# tree1.net
KiCad netlist of a schematic drawn in EAGLE
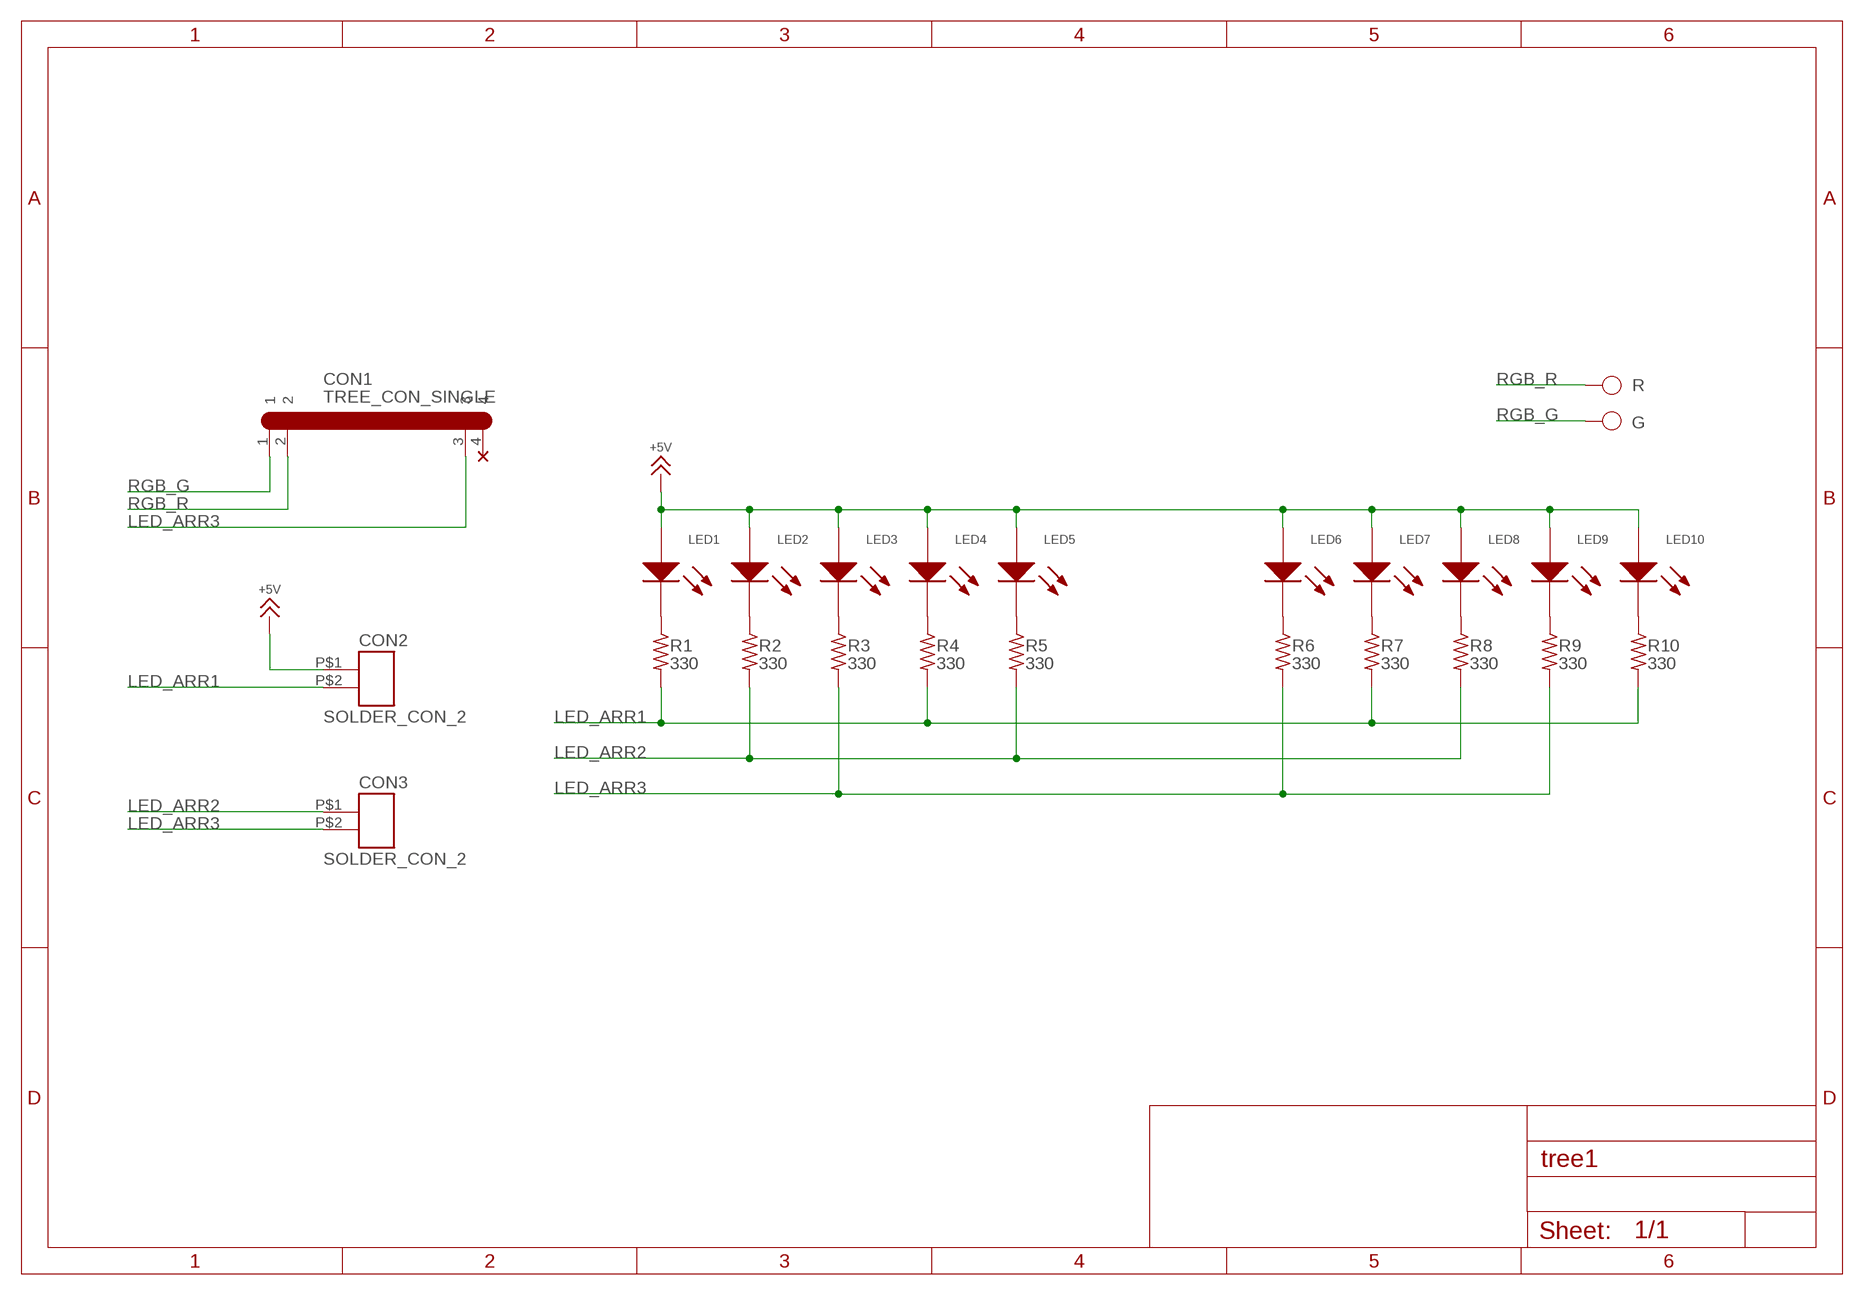
[diagram p0: schematic, sheet 1]

(export (version "E")
  (design (tool "Eeschema 10.0.6"))
  (components
    (comp (ref "CON1")
      (value "TREE_CON_SINGLE")
      (footprint "eagle-import:TREE_CON_SINGLE")
      (libsource (lib "eagle-import") (part "TREE_CON_SINGLE"))
    )
    (comp (ref "CON2")
      (value "SOLDER_CON_2")
      (footprint "eagle-import:SOLDER_CON_2")
      (libsource (lib "eagle-import") (part "SOLDER_CON_2"))
    )
    (comp (ref "CON3")
      (value "SOLDER_CON_2")
      (footprint "eagle-import:SOLDER_CON_2")
      (libsource (lib "eagle-import") (part "SOLDER_CON_2"))
    )
    (comp (ref "G") (value "TP") (footprint "eagle-import:TP") (libsource (lib "eagle-import") (part "TP")))
    (comp (ref "LED1")
      (value "LED_BEN")
      (footprint "eagle-import:LED_5MM_BEN")
      (libsource (lib "eagle-import") (part "LED_BEN"))
    )
    (comp (ref "LED2")
      (value "LED_BEN")
      (footprint "eagle-import:LED_5MM_BEN")
      (libsource (lib "eagle-import") (part "LED_BEN"))
    )
    (comp (ref "LED3")
      (value "LED_BEN")
      (footprint "eagle-import:LED_5MM_BEN")
      (libsource (lib "eagle-import") (part "LED_BEN"))
    )
    (comp (ref "LED4")
      (value "LED_BEN")
      (footprint "eagle-import:LED_5MM_BEN")
      (libsource (lib "eagle-import") (part "LED_BEN"))
    )
    (comp (ref "LED5")
      (value "LED_BEN")
      (footprint "eagle-import:LED_5MM_BEN")
      (libsource (lib "eagle-import") (part "LED_BEN"))
    )
    (comp (ref "LED6")
      (value "LED_BEN")
      (footprint "eagle-import:LED_5MM_BEN")
      (libsource (lib "eagle-import") (part "LED_BEN"))
    )
    (comp (ref "LED7")
      (value "LED_BEN")
      (footprint "eagle-import:LED_5MM_BEN")
      (libsource (lib "eagle-import") (part "LED_BEN"))
    )
    (comp (ref "LED8")
      (value "LED_BEN")
      (footprint "eagle-import:LED_5MM_BEN")
      (libsource (lib "eagle-import") (part "LED_BEN"))
    )
    (comp (ref "LED9")
      (value "LED_BEN")
      (footprint "eagle-import:LED_5MM_BEN")
      (libsource (lib "eagle-import") (part "LED_BEN"))
    )
    (comp (ref "LED10")
      (value "LED_BEN")
      (footprint "eagle-import:LED_5MM_BEN")
      (libsource (lib "eagle-import") (part "LED_BEN"))
    )
    (comp (ref "R") (value "TP") (footprint "eagle-import:TP") (libsource (lib "eagle-import") (part "TP")))
    (comp (ref "R1")
      (value "330")
      (footprint "eagle-import:SMD2012")
      (libsource (lib "eagle-import") (part "RES_2012"))
    )
    (comp (ref "R2")
      (value "330")
      (footprint "eagle-import:SMD2012")
      (libsource (lib "eagle-import") (part "RES_2012"))
    )
    (comp (ref "R3")
      (value "330")
      (footprint "eagle-import:SMD2012")
      (libsource (lib "eagle-import") (part "RES_2012"))
    )
    (comp (ref "R4")
      (value "330")
      (footprint "eagle-import:SMD2012")
      (libsource (lib "eagle-import") (part "RES_2012"))
    )
    (comp (ref "R5")
      (value "330")
      (footprint "eagle-import:SMD2012")
      (libsource (lib "eagle-import") (part "RES_2012"))
    )
    (comp (ref "R6")
      (value "330")
      (footprint "eagle-import:SMD2012")
      (libsource (lib "eagle-import") (part "RES_2012"))
    )
    (comp (ref "R7")
      (value "330")
      (footprint "eagle-import:SMD2012")
      (libsource (lib "eagle-import") (part "RES_2012"))
    )
    (comp (ref "R8")
      (value "330")
      (footprint "eagle-import:SMD2012")
      (libsource (lib "eagle-import") (part "RES_2012"))
    )
    (comp (ref "R9")
      (value "330")
      (footprint "eagle-import:SMD2012")
      (libsource (lib "eagle-import") (part "RES_2012"))
    )
    (comp (ref "R10")
      (value "330")
      (footprint "eagle-import:SMD2012")
      (libsource (lib "eagle-import") (part "RES_2012"))
    )
  )
  (nets
    (net (code "1") (name "+5V") (class "Default")
      (node (ref "CON2") (pin "P$1") (pinfunction "P$1_P$1") (pintype "passive"))
      (node (ref "LED1") (pin "1") (pinfunction "P$1_1") (pintype "passive"))
      (node (ref "LED10") (pin "1") (pinfunction "P$1_1") (pintype "passive"))
      (node (ref "LED2") (pin "1") (pinfunction "P$1_1") (pintype "passive"))
      (node (ref "LED3") (pin "1") (pinfunction "P$1_1") (pintype "passive"))
      (node (ref "LED4") (pin "1") (pinfunction "P$1_1") (pintype "passive"))
      (node (ref "LED5") (pin "1") (pinfunction "P$1_1") (pintype "passive"))
      (node (ref "LED6") (pin "1") (pinfunction "P$1_1") (pintype "passive"))
      (node (ref "LED7") (pin "1") (pinfunction "P$1_1") (pintype "passive"))
      (node (ref "LED8") (pin "1") (pinfunction "P$1_1") (pintype "passive"))
      (node (ref "LED9") (pin "1") (pinfunction "P$1_1") (pintype "passive"))
    )
    (net (code "2") (name "/LED_ARR1") (class "Default")
      (node (ref "CON2") (pin "P$2") (pinfunction "P$2_P$2") (pintype "passive"))
      (node (ref "R1") (pin "2") (pinfunction "2_2") (pintype "passive"))
      (node (ref "R10") (pin "2") (pinfunction "2_2") (pintype "passive"))
      (node (ref "R4") (pin "2") (pinfunction "2_2") (pintype "passive"))
      (node (ref "R7") (pin "2") (pinfunction "2_2") (pintype "passive"))
    )
    (net (code "3") (name "/LED_ARR2") (class "Default")
      (node (ref "CON3") (pin "P$1") (pinfunction "P$1_P$1") (pintype "passive"))
      (node (ref "R2") (pin "2") (pinfunction "2_2") (pintype "passive"))
      (node (ref "R5") (pin "2") (pinfunction "2_2") (pintype "passive"))
      (node (ref "R8") (pin "2") (pinfunction "2_2") (pintype "passive"))
    )
    (net (code "4") (name "/LED_ARR3") (class "Default")
      (node (ref "CON1") (pin "3") (pinfunction "3_3") (pintype "passive"))
      (node (ref "CON3") (pin "P$2") (pinfunction "P$2_P$2") (pintype "passive"))
      (node (ref "R3") (pin "2") (pinfunction "2_2") (pintype "passive"))
      (node (ref "R6") (pin "2") (pinfunction "2_2") (pintype "passive"))
      (node (ref "R9") (pin "2") (pinfunction "2_2") (pintype "passive"))
    )
    (net (code "5") (name "/RGB_G") (class "Default")
      (node (ref "CON1") (pin "1") (pinfunction "1_1") (pintype "passive"))
      (node (ref "G") (pin "1") (pinfunction "P$1_1") (pintype "passive"))
    )
    (net (code "6") (name "/RGB_R") (class "Default")
      (node (ref "CON1") (pin "2") (pinfunction "2_2") (pintype "passive"))
      (node (ref "R") (pin "1") (pinfunction "P$1_1") (pintype "passive"))
    )
    (net (code "7") (name "Net-(LED1-P$2)") (class "Default")
      (node (ref "LED1") (pin "2") (pinfunction "P$2_2") (pintype "passive"))
      (node (ref "R1") (pin "1") (pinfunction "1_1") (pintype "passive"))
    )
    (net (code "8") (name "Net-(LED2-P$2)") (class "Default")
      (node (ref "LED2") (pin "2") (pinfunction "P$2_2") (pintype "passive"))
      (node (ref "R2") (pin "1") (pinfunction "1_1") (pintype "passive"))
    )
    (net (code "9") (name "Net-(LED3-P$2)") (class "Default")
      (node (ref "LED3") (pin "2") (pinfunction "P$2_2") (pintype "passive"))
      (node (ref "R3") (pin "1") (pinfunction "1_1") (pintype "passive"))
    )
    (net (code "10") (name "Net-(LED4-P$2)") (class "Default")
      (node (ref "LED4") (pin "2") (pinfunction "P$2_2") (pintype "passive"))
      (node (ref "R4") (pin "1") (pinfunction "1_1") (pintype "passive"))
    )
    (net (code "11") (name "Net-(LED5-P$2)") (class "Default")
      (node (ref "LED5") (pin "2") (pinfunction "P$2_2") (pintype "passive"))
      (node (ref "R5") (pin "1") (pinfunction "1_1") (pintype "passive"))
    )
    (net (code "12") (name "Net-(LED6-P$2)") (class "Default")
      (node (ref "LED6") (pin "2") (pinfunction "P$2_2") (pintype "passive"))
      (node (ref "R6") (pin "1") (pinfunction "1_1") (pintype "passive"))
    )
    (net (code "13") (name "Net-(LED7-P$2)") (class "Default")
      (node (ref "LED7") (pin "2") (pinfunction "P$2_2") (pintype "passive"))
      (node (ref "R7") (pin "1") (pinfunction "1_1") (pintype "passive"))
    )
    (net (code "14") (name "Net-(LED8-P$2)") (class "Default")
      (node (ref "LED8") (pin "2") (pinfunction "P$2_2") (pintype "passive"))
      (node (ref "R8") (pin "1") (pinfunction "1_1") (pintype "passive"))
    )
    (net (code "15") (name "Net-(LED9-P$2)") (class "Default")
      (node (ref "LED9") (pin "2") (pinfunction "P$2_2") (pintype "passive"))
      (node (ref "R9") (pin "1") (pinfunction "1_1") (pintype "passive"))
    )
    (net (code "16") (name "Net-(LED10-P$2)") (class "Default")
      (node (ref "LED10") (pin "2") (pinfunction "P$2_2") (pintype "passive"))
      (node (ref "R10") (pin "1") (pinfunction "1_1") (pintype "passive"))
    )
    (net (code "17") (name "unconnected-(CON1-Pad4)") (class "Default")
      (node (ref "CON1") (pin "4") (pinfunction "4_4") (pintype "passive"))
    )
  )
)
